# DC.net
KiCad netlist of a schematic drawn in Altium Designer
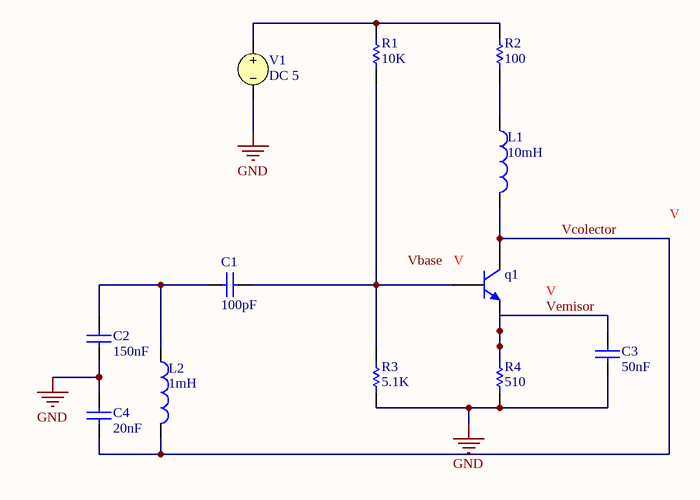
[diagram p0: DC.SchDoc]

(export (version "E")
  (design (tool "Eeschema 10.0.6"))
  (components
    (comp (ref "C1")
      (value "100pF")
      (description "Capacitor")
      (libsource (lib "Simulation Generic Components") (part "Capacitor"))
    )
    (comp (ref "C2")
      (value "150nF")
      (description "Capacitor")
      (libsource (lib "Simulation Generic Components") (part "Capacitor"))
    )
    (comp (ref "C3")
      (value "50nF")
      (description "Capacitor")
      (libsource (lib "Simulation Generic Components") (part "Capacitor"))
    )
    (comp (ref "C4")
      (value "20nF")
      (description "Capacitor")
      (libsource (lib "Simulation Generic Components") (part "Capacitor"))
    )
    (comp (ref "L1")
      (value "10mH")
      (description "Inductor")
      (libsource (lib "Simulation Generic Components") (part "Inductor"))
    )
    (comp (ref "L2")
      (value "1mH")
      (description "Inductor")
      (libsource (lib "Simulation Generic Components") (part "Inductor"))
    )
    (comp (ref "q1")
      (value "Bipolar NPN 3 Pins Transistor VBIC Model")
      (libsource (lib "Simulation Generic Components") (part "BJT NPN VBIC"))
    )
    (comp (ref "R1")
      (value "10K")
      (description "Resistor")
      (libsource (lib "Simulation Generic Components") (part "Resistor"))
    )
    (comp (ref "R2")
      (value "100")
      (description "Resistor")
      (libsource (lib "Simulation Generic Components") (part "Resistor"))
    )
    (comp (ref "R3")
      (value "5.1K")
      (description "Resistor")
      (libsource (lib "Simulation Generic Components") (part "Resistor"))
    )
    (comp (ref "R4")
      (value "510")
      (description "Resistor")
      (libsource (lib "Simulation Generic Components") (part "Resistor"))
    )
    (comp (ref "V1")
      (value "DC 5")
      (description "Voltage Source")
      (fields (field (name "PUBLISHER") "Altium Limited"))
      (libsource (lib "Simulation Generic Components") (part "VSRC"))
    )
  )
  (nets
    (net (code "2") (name "/Vcolector") (class "Default")
      (node (ref "C4") (pin "2") (pinfunction "2_2") (pintype "passive"))
      (node (ref "L1") (pin "2") (pinfunction "2_2") (pintype "passive"))
      (node (ref "L2") (pin "2") (pinfunction "2_2") (pintype "passive"))
      (node (ref "q1") (pin "1") (pinfunction "C_1") (pintype "passive"))
    )
    (net (code "3") (name "/Vemisor") (class "Default")
      (node (ref "C3") (pin "1") (pinfunction "1_1") (pintype "passive"))
      (node (ref "R4") (pin "1") (pinfunction "1_1") (pintype "passive"))
      (node (ref "q1") (pin "3") (pinfunction "E_3") (pintype "passive"))
    )
    (net (code "4") (name "GND") (class "Default")
      (node (ref "C2") (pin "2") (pinfunction "2_2") (pintype "passive"))
      (node (ref "C3") (pin "2") (pinfunction "2_2") (pintype "passive"))
      (node (ref "C4") (pin "1") (pinfunction "1_1") (pintype "passive"))
      (node (ref "R3") (pin "2") (pinfunction "2_2") (pintype "passive"))
      (node (ref "R4") (pin "2") (pinfunction "2_2") (pintype "passive"))
      (node (ref "V1") (pin "2") (pinfunction "2_2") (pintype "passive"))
    )
    (net (code "5") (name "Net-(C1-Pad2)") (class "Default")
      (node (ref "C1") (pin "2") (pinfunction "2_2") (pintype "passive"))
      (node (ref "C2") (pin "1") (pinfunction "1_1") (pintype "passive"))
      (node (ref "L2") (pin "1") (pinfunction "1_1") (pintype "passive"))
    )
    (net (code "6") (name "Net-(L1-Pad1)") (class "Default")
      (node (ref "L1") (pin "1") (pinfunction "1_1") (pintype "passive"))
      (node (ref "R2") (pin "2") (pinfunction "2_2") (pintype "passive"))
    )
    (net (code "7") (name "Net-(R1-Pad1)") (class "Default")
      (node (ref "R1") (pin "1") (pinfunction "1_1") (pintype "passive"))
      (node (ref "R2") (pin "1") (pinfunction "1_1") (pintype "passive"))
      (node (ref "V1") (pin "1") (pinfunction "1_1") (pintype "passive"))
    )
    (net (code "8") (name "Net-(q1-B)") (class "Default")
      (node (ref "C1") (pin "1") (pinfunction "1_1") (pintype "passive"))
      (node (ref "R1") (pin "2") (pinfunction "2_2") (pintype "passive"))
      (node (ref "R3") (pin "1") (pinfunction "1_1") (pintype "passive"))
      (node (ref "q1") (pin "2") (pinfunction "B_2") (pintype "passive"))
    )
  )
)
